# BaseMachine_Sequencer_UI_2.net
KiCad netlist of a schematic drawn in EAGLE
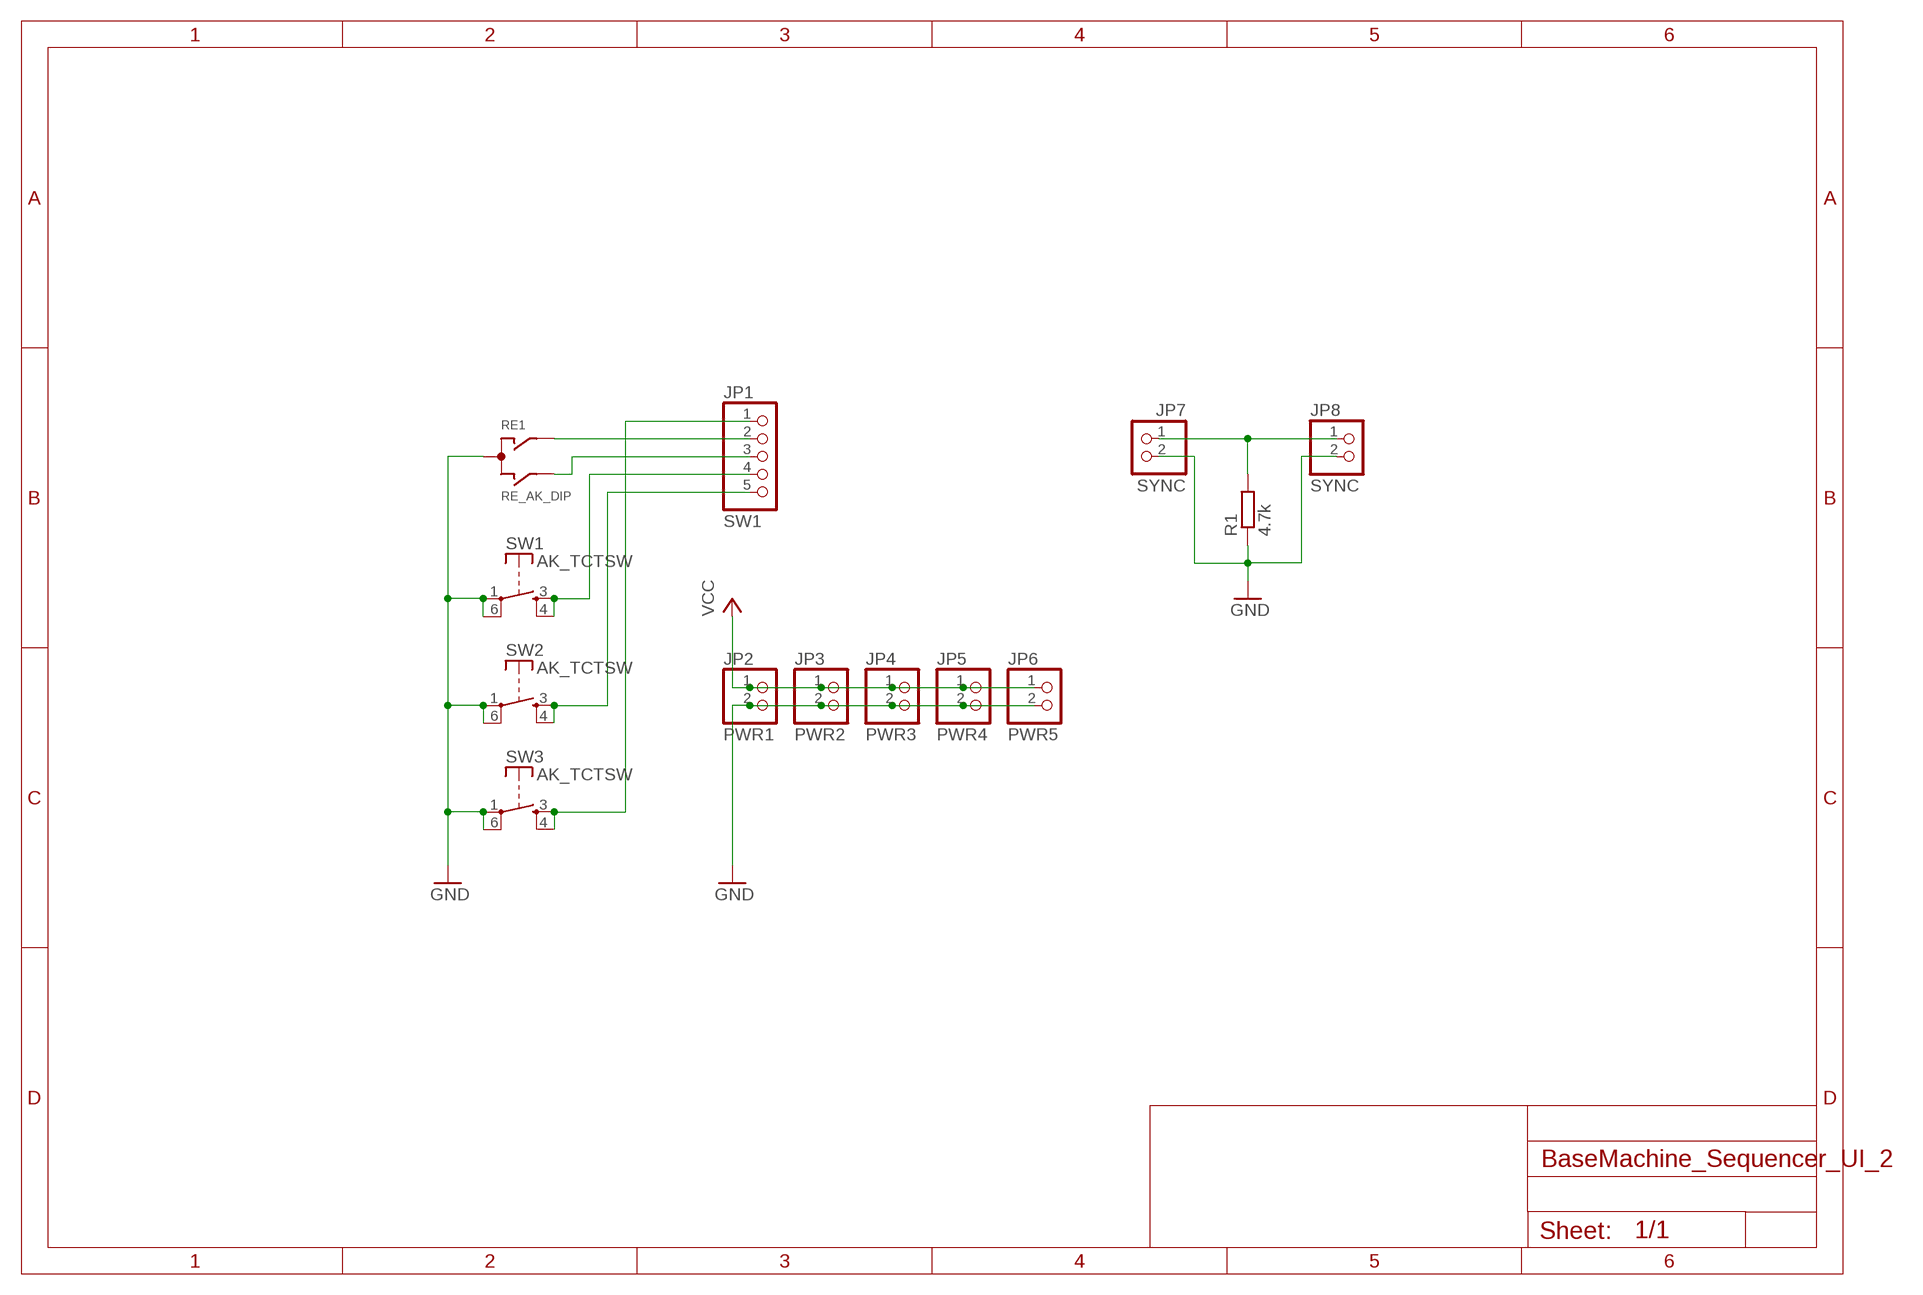
[diagram p0: schematic, sheet 1]

(export (version "E")
  (design (tool "Eeschema 10.0.6"))
  (components
    (comp (ref "JP1")
      (value "SW1")
      (footprint "eagle-import:1X05_90")
      (libsource (lib "eagle-import") (part "PINHD-1X5/90"))
    )
    (comp (ref "JP2")
      (value "PWR1")
      (footprint "eagle-import:1X02_90")
      (libsource (lib "eagle-import") (part "PINHD-1X2/90"))
    )
    (comp (ref "JP3")
      (value "PWR2")
      (footprint "eagle-import:1X02")
      (libsource (lib "eagle-import") (part "PINHD-1X2"))
    )
    (comp (ref "JP4")
      (value "PWR3")
      (footprint "eagle-import:1X02")
      (libsource (lib "eagle-import") (part "PINHD-1X2"))
    )
    (comp (ref "JP5")
      (value "PWR4")
      (footprint "eagle-import:1X02")
      (libsource (lib "eagle-import") (part "PINHD-1X2"))
    )
    (comp (ref "JP6")
      (value "PWR5")
      (footprint "eagle-import:1X02")
      (libsource (lib "eagle-import") (part "PINHD-1X2"))
    )
    (comp (ref "JP7")
      (value "SYNC")
      (footprint "eagle-import:1X02_90")
      (libsource (lib "eagle-import") (part "PINHD-1X2/90"))
    )
    (comp (ref "JP8")
      (value "SYNC")
      (footprint "eagle-import:1X02")
      (libsource (lib "eagle-import") (part "PINHD-1X2"))
    )
    (comp (ref "R1")
      (value "4.7k")
      (footprint "eagle-import:0207_7")
      (libsource (lib "eagle-import") (part "R-EU_0207/7"))
    )
    (comp (ref "RE1")
      (value "RE_AK_DIP")
      (footprint "eagle-import:RE_AK_DIP")
      (libsource (lib "eagle-import") (part "RE_AK_DIP"))
    )
    (comp (ref "SW1")
      (value "AK_TCTSW")
      (footprint "eagle-import:TME1")
      (libsource (lib "eagle-import") (part "AK_TCTSW"))
    )
    (comp (ref "SW2")
      (value "AK_TCTSW")
      (footprint "eagle-import:TME1")
      (libsource (lib "eagle-import") (part "AK_TCTSW"))
    )
    (comp (ref "SW3")
      (value "AK_TCTSW")
      (footprint "eagle-import:TME1")
      (libsource (lib "eagle-import") (part "AK_TCTSW"))
    )
  )
  (nets
    (net (code "1") (name "GND") (class "Default")
      (node (ref "JP2") (pin "2") (pinfunction "2_2") (pintype "passive"))
      (node (ref "JP3") (pin "2") (pinfunction "2_2") (pintype "passive"))
      (node (ref "JP4") (pin "2") (pinfunction "2_2") (pintype "passive"))
      (node (ref "JP5") (pin "2") (pinfunction "2_2") (pintype "passive"))
      (node (ref "JP6") (pin "2") (pinfunction "2_2") (pintype "passive"))
      (node (ref "JP7") (pin "2") (pinfunction "2_2") (pintype "passive"))
      (node (ref "JP8") (pin "2") (pinfunction "2_2") (pintype "passive"))
      (node (ref "R1") (pin "1") (pinfunction "1_1") (pintype "passive"))
      (node (ref "RE1") (pin "P$3") (pinfunction "C_P$3") (pintype "passive"))
      (node (ref "SW1") (pin "1") (pinfunction "P_1") (pintype "passive"))
      (node (ref "SW1") (pin "6") (pinfunction "P_6") (pintype "passive"))
      (node (ref "SW2") (pin "1") (pinfunction "P_1") (pintype "passive"))
      (node (ref "SW2") (pin "6") (pinfunction "P_6") (pintype "passive"))
      (node (ref "SW3") (pin "1") (pinfunction "P_1") (pintype "passive"))
      (node (ref "SW3") (pin "6") (pinfunction "P_6") (pintype "passive"))
    )
    (net (code "2") (name "Net-(JP1-Pad1)") (class "Default")
      (node (ref "JP1") (pin "1") (pinfunction "1_1") (pintype "passive"))
      (node (ref "SW3") (pin "3") (pinfunction "S_3") (pintype "passive"))
      (node (ref "SW3") (pin "4") (pinfunction "S_4") (pintype "passive"))
    )
    (net (code "3") (name "Net-(JP1-Pad4)") (class "Default")
      (node (ref "JP1") (pin "4") (pinfunction "4_4") (pintype "passive"))
      (node (ref "SW1") (pin "3") (pinfunction "S_3") (pintype "passive"))
      (node (ref "SW1") (pin "4") (pinfunction "S_4") (pintype "passive"))
    )
    (net (code "4") (name "Net-(JP1-Pad5)") (class "Default")
      (node (ref "JP1") (pin "5") (pinfunction "5_5") (pintype "passive"))
      (node (ref "SW2") (pin "3") (pinfunction "S_3") (pintype "passive"))
      (node (ref "SW2") (pin "4") (pinfunction "S_4") (pintype "passive"))
    )
    (net (code "5") (name "Net-(JP7-Pad1)") (class "Default")
      (node (ref "JP7") (pin "1") (pinfunction "1_1") (pintype "passive"))
      (node (ref "JP8") (pin "1") (pinfunction "1_1") (pintype "passive"))
      (node (ref "R1") (pin "2") (pinfunction "2_2") (pintype "passive"))
    )
    (net (code "6") (name "Net-(RE1-A)") (class "Default")
      (node (ref "JP1") (pin "2") (pinfunction "2_2") (pintype "passive"))
      (node (ref "RE1") (pin "P$2") (pinfunction "A_P$2") (pintype "passive"))
    )
    (net (code "7") (name "Net-(RE1-B)") (class "Default")
      (node (ref "JP1") (pin "3") (pinfunction "3_3") (pintype "passive"))
      (node (ref "RE1") (pin "P$4") (pinfunction "B_P$4") (pintype "passive"))
    )
    (net (code "8") (name "VCC") (class "Default")
      (node (ref "JP2") (pin "1") (pinfunction "1_1") (pintype "passive"))
      (node (ref "JP3") (pin "1") (pinfunction "1_1") (pintype "passive"))
      (node (ref "JP4") (pin "1") (pinfunction "1_1") (pintype "passive"))
      (node (ref "JP5") (pin "1") (pinfunction "1_1") (pintype "passive"))
      (node (ref "JP6") (pin "1") (pinfunction "1_1") (pintype "passive"))
    )
  )
)
